# Schematic.net
KiCad netlist of a schematic drawn in EasyEDA
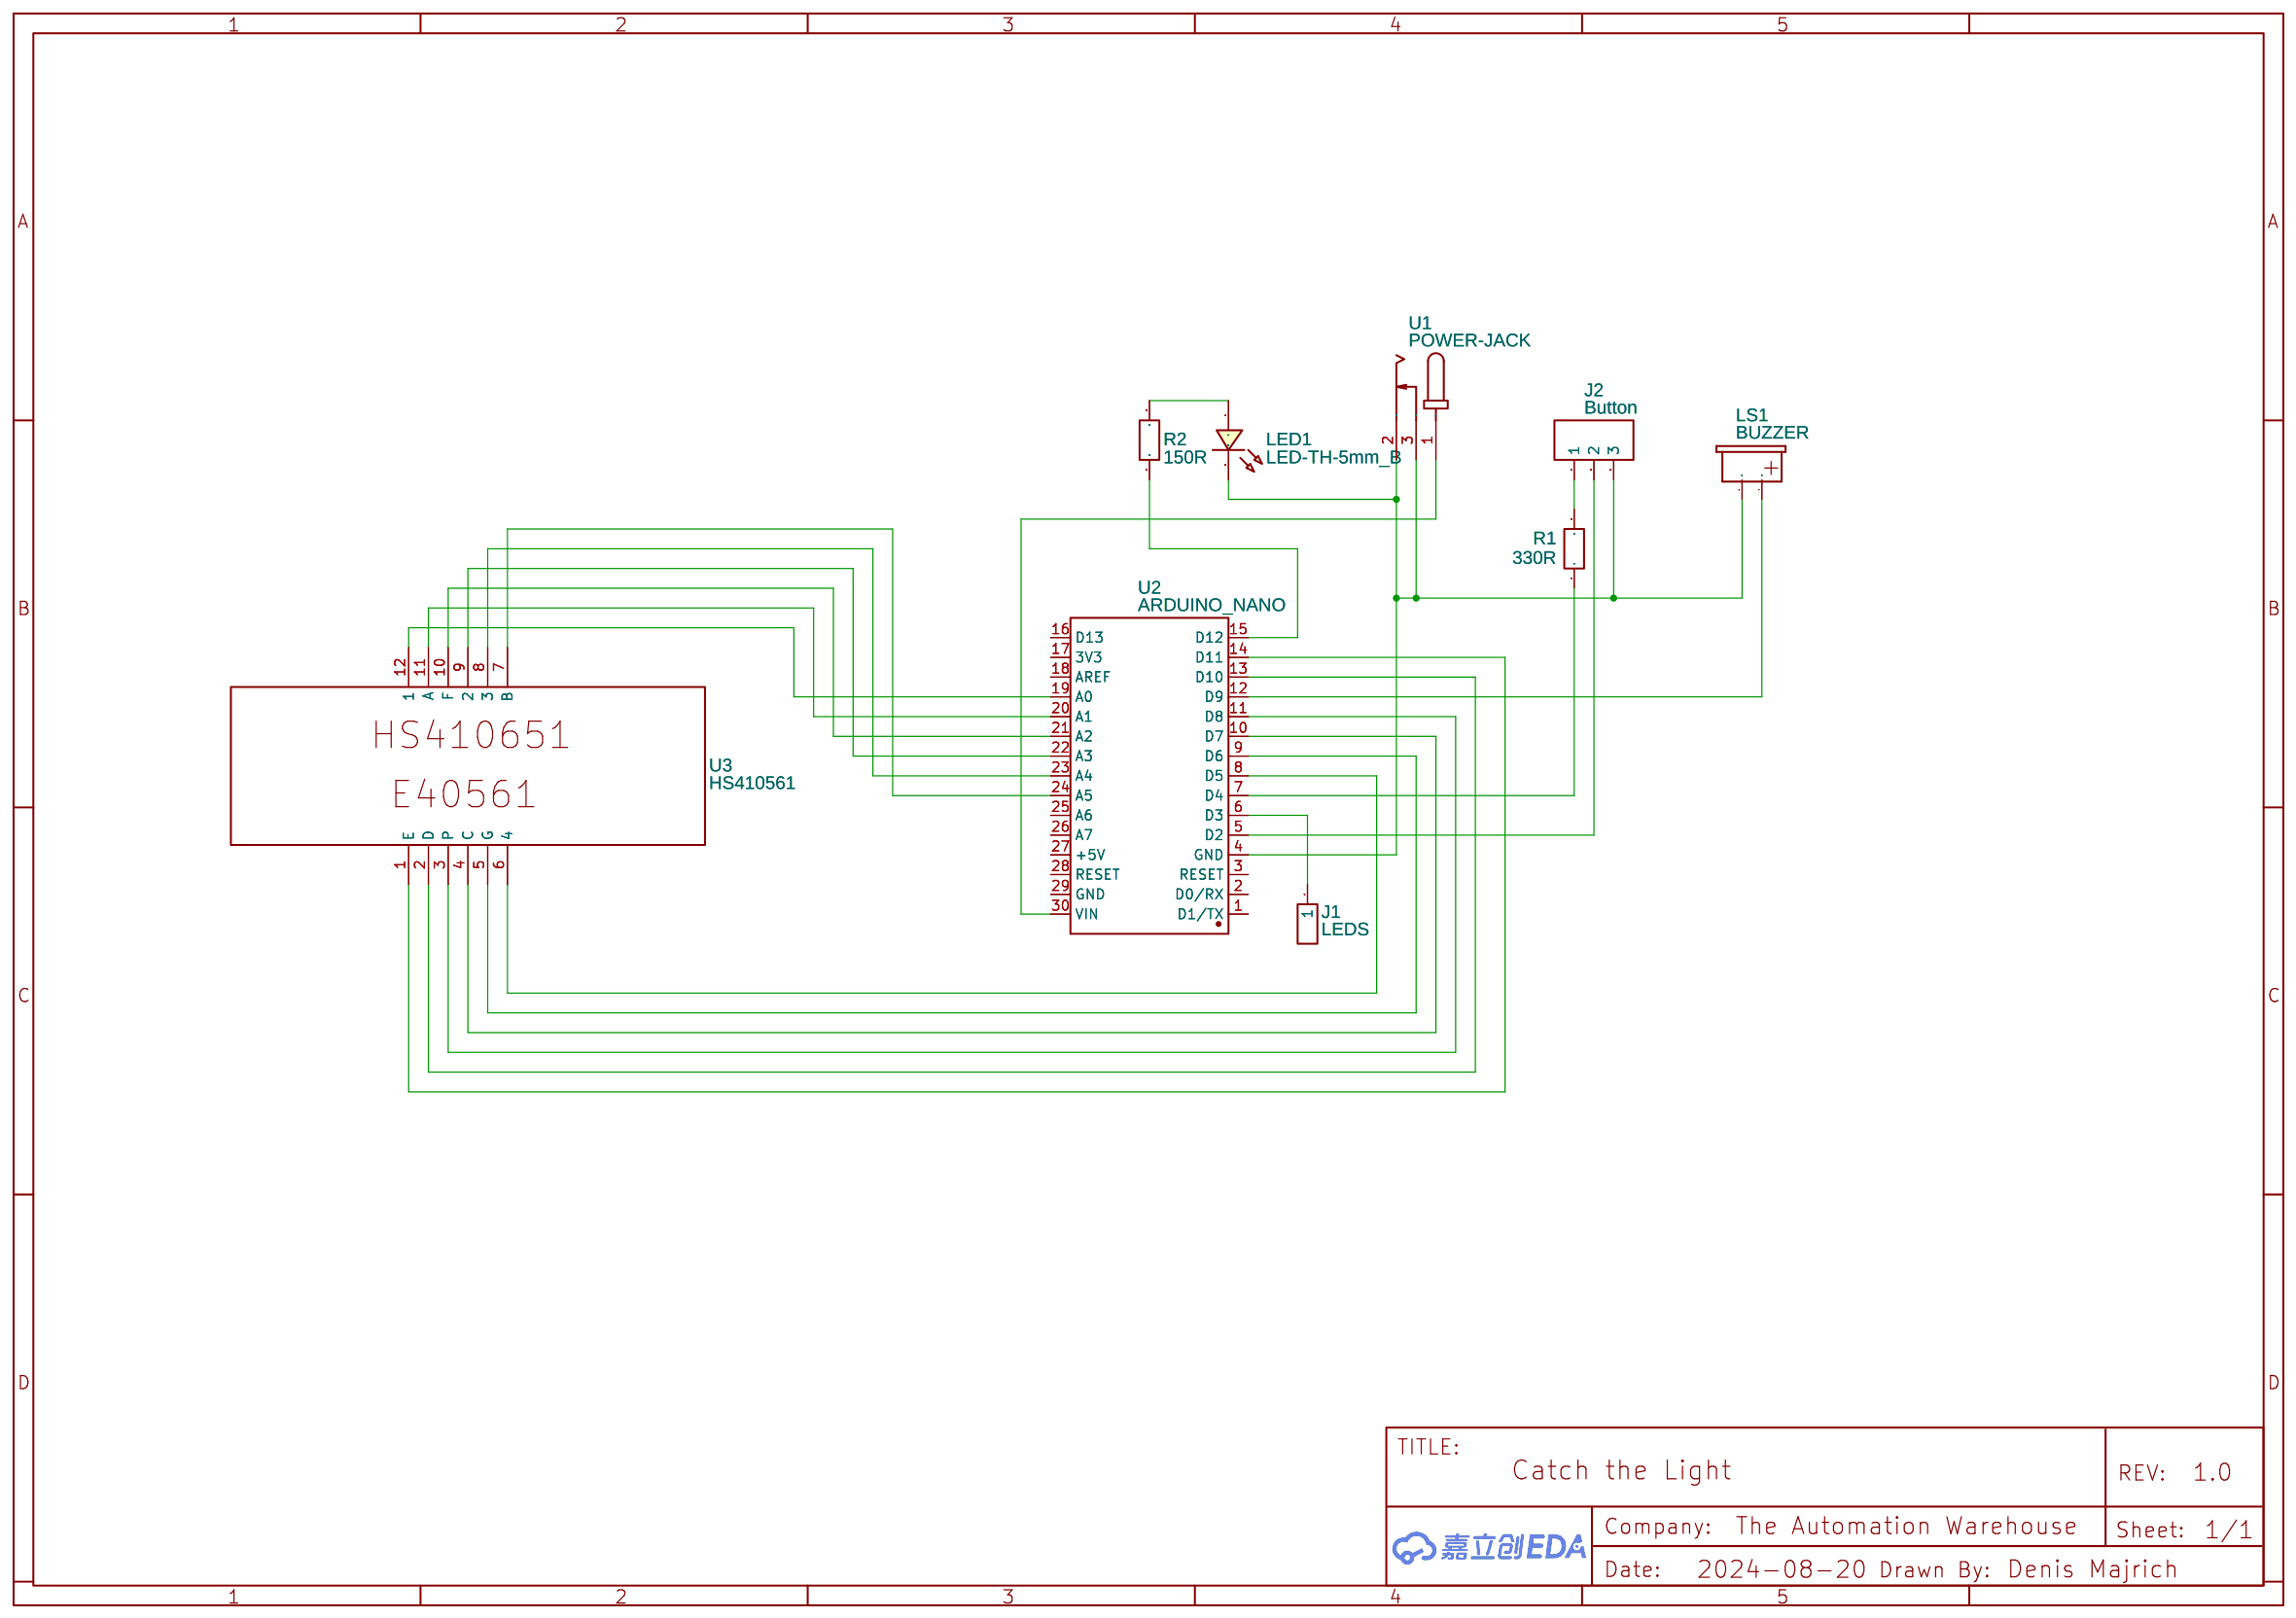
[diagram p0: schematic sheet]

(export (version "E")
  (design (tool "Eeschema 10.0.6"))
  (components
    (comp (ref "J1")
      (value "LEDS")
      (fields (field (name "BOM_Supplier Part") "C81276"))
      (libsource (lib "") (part "HDR-M-2.54_1x1"))
    )
    (comp (ref "J2")
      (value "Button")
      (fields (field (name "BOM_Supplier Part") "C180248"))
      (libsource (lib "") (part "HDR-M-2.54_1x3"))
    )
    (comp (ref "LED1") (value "LED-TH-5mm_B") (libsource (lib "") (part "LED-TH-5mm_B")))
    (comp (ref "LS1") (value "BUZZER") (libsource (lib "") (part "BUZZER-passive")))
    (comp (ref "R1") (value "330R") (libsource (lib "") (part "R_AXIAL-0.4_EU")))
    (comp (ref "R2") (value "150R") (libsource (lib "") (part "R_AXIAL-0.4_EU")))
    (comp (ref "U1")
      (value "POWER-JACK")
      (fields (field (name "BOM_Supplier Part") "C9900001795"))
      (libsource (lib "") (part "POWER-JACK"))
    )
    (comp (ref "U2") (value "ARDUINO_NANO") (libsource (lib "") (part "ARDUINO_NANO")))
    (comp (ref "U3")
      (value "HS410561")
      (fields (field (name "BOM_Supplier Part") "ALI"))
      (libsource (lib "") (part "HS410561"))
    )
  )
  (nets
    (net (code "1") (name "Net-(J2-Pad1)") (class "Default")
      (node (ref "J2") (pin "1") (pinfunction "1_1") (pintype "input"))
      (node (ref "R1") (pin "2") (pinfunction "2_2") (pintype "unspecified"))
    )
    (net (code "2") (name "Net-(LED1-Pad1)") (class "Default")
      (node (ref "LED1") (pin "1") (pinfunction "1_1") (pintype "unspecified"))
      (node (ref "R2") (pin "2") (pinfunction "2_2") (pintype "unspecified"))
    )
    (net (code "3") (name "Net-(LS1-1)") (class "Default")
      (node (ref "J2") (pin "3") (pinfunction "3_3") (pintype "input"))
      (node (ref "LED1") (pin "2") (pinfunction "2_2") (pintype "unspecified"))
      (node (ref "LS1") (pin "+") (pinfunction "1_+") (pintype "bidirectional"))
      (node (ref "U1") (pin "2") (pinfunction "2_2") (pintype "unspecified"))
      (node (ref "U1") (pin "3") (pinfunction "3_3") (pintype "unspecified"))
      (node (ref "U2") (pin "4") (pinfunction "GND_4") (pintype "unspecified"))
    )
    (net (code "4") (name "Net-(LS1-2)") (class "Default")
      (node (ref "LS1") (pin "-") (pinfunction "2_-") (pintype "bidirectional"))
      (node (ref "U2") (pin "12") (pinfunction "D9_12") (pintype "unspecified"))
    )
    (net (code "5") (name "Net-(U2-A0)") (class "Default")
      (node (ref "U2") (pin "19") (pinfunction "A0_19") (pintype "unspecified"))
      (node (ref "U3") (pin "12") (pinfunction "1_12") (pintype "unspecified"))
    )
    (net (code "6") (name "Net-(U2-A1)") (class "Default")
      (node (ref "U2") (pin "20") (pinfunction "A1_20") (pintype "unspecified"))
      (node (ref "U3") (pin "11") (pinfunction "A_11") (pintype "unspecified"))
    )
    (net (code "7") (name "Net-(U2-A2)") (class "Default")
      (node (ref "U2") (pin "21") (pinfunction "A2_21") (pintype "unspecified"))
      (node (ref "U3") (pin "10") (pinfunction "F_10") (pintype "unspecified"))
    )
    (net (code "8") (name "Net-(U2-A3)") (class "Default")
      (node (ref "U2") (pin "22") (pinfunction "A3_22") (pintype "unspecified"))
      (node (ref "U3") (pin "9") (pinfunction "2_9") (pintype "unspecified"))
    )
    (net (code "9") (name "Net-(U2-A4)") (class "Default")
      (node (ref "U2") (pin "23") (pinfunction "A4_23") (pintype "unspecified"))
      (node (ref "U3") (pin "8") (pinfunction "3_8") (pintype "unspecified"))
    )
    (net (code "10") (name "Net-(U2-A5)") (class "Default")
      (node (ref "U2") (pin "24") (pinfunction "A5_24") (pintype "unspecified"))
      (node (ref "U3") (pin "7") (pinfunction "B_7") (pintype "unspecified"))
    )
    (net (code "11") (name "Net-(U2-D2)") (class "Default")
      (node (ref "J2") (pin "2") (pinfunction "2_2") (pintype "input"))
      (node (ref "U2") (pin "5") (pinfunction "D2_5") (pintype "unspecified"))
    )
    (net (code "12") (name "Net-(U2-D3)") (class "Default")
      (node (ref "J1") (pin "1") (pinfunction "1_1") (pintype "input"))
      (node (ref "U2") (pin "6") (pinfunction "D3_6") (pintype "unspecified"))
    )
    (net (code "13") (name "Net-(U2-D4)") (class "Default")
      (node (ref "R1") (pin "1") (pinfunction "1_1") (pintype "unspecified"))
      (node (ref "U2") (pin "7") (pinfunction "D4_7") (pintype "unspecified"))
    )
    (net (code "14") (name "Net-(U2-D5)") (class "Default")
      (node (ref "U2") (pin "8") (pinfunction "D5_8") (pintype "unspecified"))
      (node (ref "U3") (pin "6") (pinfunction "4_6") (pintype "unspecified"))
    )
    (net (code "15") (name "Net-(U2-D6)") (class "Default")
      (node (ref "U2") (pin "9") (pinfunction "D6_9") (pintype "unspecified"))
      (node (ref "U3") (pin "5") (pinfunction "G_5") (pintype "unspecified"))
    )
    (net (code "16") (name "Net-(U2-D7)") (class "Default")
      (node (ref "U2") (pin "10") (pinfunction "D7_10") (pintype "unspecified"))
      (node (ref "U3") (pin "4") (pinfunction "C_4") (pintype "unspecified"))
    )
    (net (code "17") (name "Net-(U2-D8)") (class "Default")
      (node (ref "U2") (pin "11") (pinfunction "D8_11") (pintype "unspecified"))
      (node (ref "U3") (pin "3") (pinfunction "P_3") (pintype "unspecified"))
    )
    (net (code "18") (name "Net-(U2-D10)") (class "Default")
      (node (ref "U2") (pin "13") (pinfunction "D10_13") (pintype "unspecified"))
      (node (ref "U3") (pin "2") (pinfunction "D_2") (pintype "unspecified"))
    )
    (net (code "19") (name "Net-(U2-D11)") (class "Default")
      (node (ref "U2") (pin "14") (pinfunction "D11_14") (pintype "unspecified"))
      (node (ref "U3") (pin "1") (pinfunction "E_1") (pintype "unspecified"))
    )
    (net (code "20") (name "Net-(U2-D12)") (class "Default")
      (node (ref "R2") (pin "1") (pinfunction "1_1") (pintype "unspecified"))
      (node (ref "U2") (pin "15") (pinfunction "D12_15") (pintype "unspecified"))
    )
    (net (code "21") (name "Net-(U2-VIN)") (class "Default")
      (node (ref "U1") (pin "1") (pinfunction "1_1") (pintype "unspecified"))
      (node (ref "U2") (pin "30") (pinfunction "VIN_30") (pintype "unspecified"))
    )
    (net (code "22") (name "unconnected-(U2-+5V-Pad27)") (class "Default")
      (node (ref "U2") (pin "27") (pinfunction "+5V_27") (pintype "unspecified"))
    )
    (net (code "23") (name "unconnected-(U2-3V3-Pad17)") (class "Default")
      (node (ref "U2") (pin "17") (pinfunction "3V3_17") (pintype "unspecified"))
    )
    (net (code "24") (name "unconnected-(U2-A6-Pad25)") (class "Default")
      (node (ref "U2") (pin "25") (pinfunction "A6_25") (pintype "unspecified"))
    )
    (net (code "25") (name "unconnected-(U2-A7-Pad26)") (class "Default")
      (node (ref "U2") (pin "26") (pinfunction "A7_26") (pintype "unspecified"))
    )
    (net (code "26") (name "unconnected-(U2-AREF-Pad18)") (class "Default")
      (node (ref "U2") (pin "18") (pinfunction "AREF_18") (pintype "unspecified"))
    )
    (net (code "27") (name "unconnected-(U2-D0{slash}RX-Pad2)") (class "Default")
      (node (ref "U2") (pin "2") (pinfunction "D0/RX_2") (pintype "unspecified"))
    )
    (net (code "28") (name "unconnected-(U2-D1{slash}TX-Pad1)") (class "Default")
      (node (ref "U2") (pin "1") (pinfunction "D1/TX_1") (pintype "unspecified"))
    )
    (net (code "29") (name "unconnected-(U2-D13-Pad16)") (class "Default")
      (node (ref "U2") (pin "16") (pinfunction "D13_16") (pintype "unspecified"))
    )
    (net (code "30") (name "unconnected-(U2-GND-Pad29)") (class "Default")
      (node (ref "U2") (pin "29") (pinfunction "GND_29") (pintype "unspecified"))
    )
    (net (code "31") (name "unconnected-(U2-RESET-Pad3)") (class "Default")
      (node (ref "U2") (pin "3") (pinfunction "RESET_3") (pintype "unspecified"))
    )
    (net (code "32") (name "unconnected-(U2-RESET-Pad28)") (class "Default")
      (node (ref "U2") (pin "28") (pinfunction "RESET_28") (pintype "unspecified"))
    )
  )
)
